# BW1098OBC_Power_Supply.net
KiCad netlist of a schematic drawn in Altium Designer
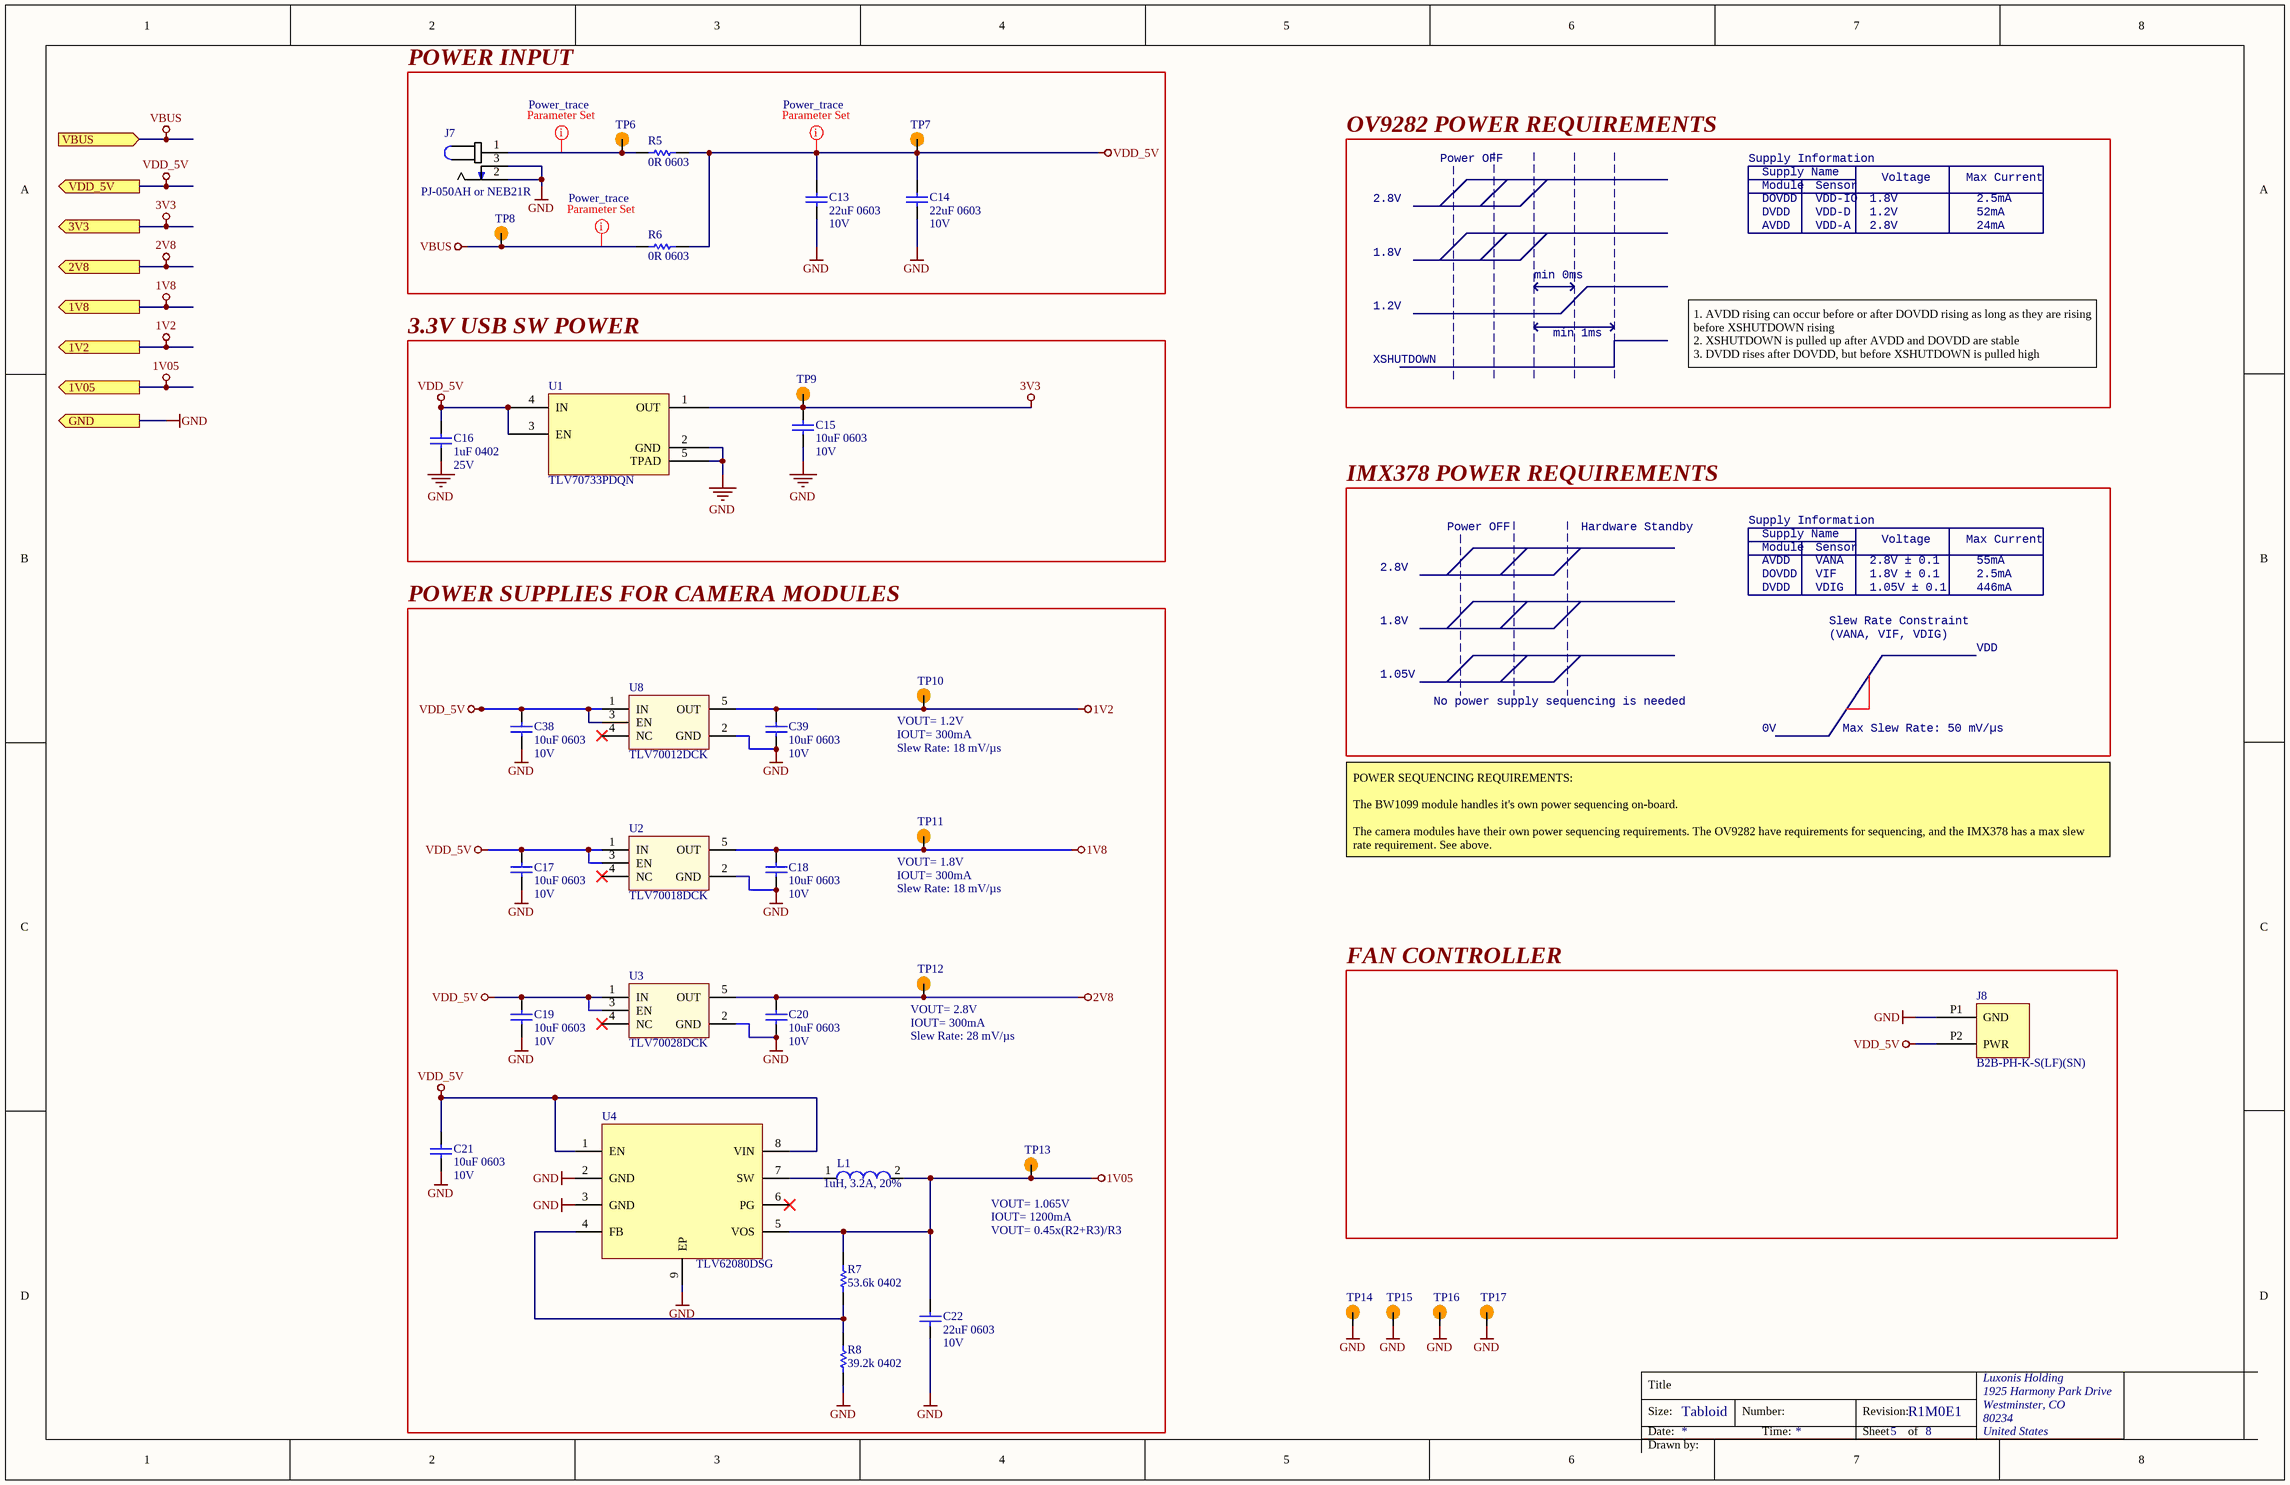
[diagram p0: BW1098OBC_Power_Supply.SchDoc]

(export (version "E")
  (design (tool "Eeschema 10.0.6"))
  (components
    (comp (ref "C13")
      (value "22uF 0603")
      (footprint "CAP_Altium_Vault_Generic:CAPC0603(1608)100_L")
      (description "CAP CER 22UF 10V X5R 0603 20%")
      (fields (field (name "TOLERANCE") "20%") (field (name "VOLTAGE RATING") "10V"))
      (libsource (lib "LuxonisMaster") (part "GRM188R61A226ME15D"))
    )
    (comp (ref "C14")
      (value "22uF 0603")
      (footprint "CAP_Altium_Vault_Generic:CAPC0603(1608)100_L")
      (description "CAP CER 22UF 10V X5R 0603 20%")
      (fields (field (name "TOLERANCE") "20%") (field (name "VOLTAGE RATING") "10V"))
      (libsource (lib "LuxonisMaster") (part "GRM188R61A226ME15D"))
    )
    (comp (ref "C15")
      (value "10uF 0603")
      (footprint "CAP_Altium_Vault_Generic:CAPC0603(1608)100_L")
      (description "CAP CER 10UF 10V X5R 0603 20%")
      (fields (field (name "TOLERANCE") "20%") (field (name "VOLTAGE RATING") "10V"))
      (libsource (lib "LuxonisMaster") (part "GRM188R61A106ME69D"))
    )
    (comp (ref "C16")
      (value "1uF 0402")
      (footprint "CAP_Altium_Vault_Generic:CAPC0402(1005)70_L")
      (description "CAP CER 1UF 25V X5R 0402 10%")
      (fields
        (field (name "TOLERANCE") "10%")
        (field (name "VOLTAGE") "25V")
        (field (name "VOLTAGE RATING") "25V")
      )
      (libsource (lib "LuxonisMaster") (part "GRM155R61E105KA12D"))
    )
    (comp (ref "C17")
      (value "10uF 0603")
      (footprint "CAP_Altium_Vault_Generic:CAPC0603(1608)100_L")
      (description "CAP CER 10UF 10V X5R 0603 20%")
      (fields (field (name "TOLERANCE") "20%") (field (name "VOLTAGE RATING") "10V"))
      (libsource (lib "LuxonisMaster") (part "GRM188R61A106ME69D"))
    )
    (comp (ref "C18")
      (value "10uF 0603")
      (footprint "CAP_Altium_Vault_Generic:CAPC0603(1608)100_L")
      (description "CAP CER 10UF 10V X5R 0603 20%")
      (fields (field (name "TOLERANCE") "20%") (field (name "VOLTAGE RATING") "10V"))
      (libsource (lib "LuxonisMaster") (part "GRM188R61A106ME69D"))
    )
    (comp (ref "C19")
      (value "10uF 0603")
      (footprint "CAP_Altium_Vault_Generic:CAPC0603(1608)100_L")
      (description "CAP CER 10UF 10V X5R 0603 20%")
      (fields (field (name "TOLERANCE") "20%") (field (name "VOLTAGE RATING") "10V"))
      (libsource (lib "LuxonisMaster") (part "GRM188R61A106ME69D"))
    )
    (comp (ref "C20")
      (value "10uF 0603")
      (footprint "CAP_Altium_Vault_Generic:CAPC0603(1608)100_L")
      (description "CAP CER 10UF 10V X5R 0603 20%")
      (fields (field (name "TOLERANCE") "20%") (field (name "VOLTAGE RATING") "10V"))
      (libsource (lib "LuxonisMaster") (part "GRM188R61A106ME69D"))
    )
    (comp (ref "C21")
      (value "10uF 0603")
      (footprint "CAP_Altium_Vault_Generic:CAPC0603(1608)100_L")
      (description "CAP CER 10UF 10V X5R 0603 20%")
      (fields (field (name "TOLERANCE") "20%") (field (name "VOLTAGE RATING") "10V"))
      (libsource (lib "LuxonisMaster") (part "GRM188R61A106ME69D"))
    )
    (comp (ref "C22")
      (value "22uF 0603")
      (footprint "CAP_Altium_Vault_Generic:CAPC0603(1608)100_L")
      (description "CAP CER 22UF 10V X5R 0603 20%")
      (fields (field (name "TOLERANCE") "20%") (field (name "VOLTAGE RATING") "10V"))
      (libsource (lib "LuxonisMaster") (part "GRM188R61A226ME15D"))
    )
    (comp (ref "C38")
      (value "10uF 0603")
      (footprint "CAP_Altium_Vault_Generic:CAPC0603(1608)100_L")
      (description "CAP CER 10UF 10V X5R 0603 20%")
      (fields (field (name "TOLERANCE") "20%") (field (name "VOLTAGE RATING") "10V"))
      (libsource (lib "LuxonisMaster") (part "GRM188R61A106ME69D"))
    )
    (comp (ref "C39")
      (value "10uF 0603")
      (footprint "CAP_Altium_Vault_Generic:CAPC0603(1608)100_L")
      (description "CAP CER 10UF 10V X5R 0603 20%")
      (fields (field (name "TOLERANCE") "20%") (field (name "VOLTAGE RATING") "10V"))
      (libsource (lib "LuxonisMaster") (part "GRM188R61A106ME69D"))
    )
    (comp (ref "J7")
      (value "PJ-050AH or NEB21R")
      (footprint "LuxonisMaster:PJ-050AH/NEB21R_COMBO")
      (description "CONN POWER PIN 2 POS RA PTH Barrel jack 2.1mm x 5.5mm combo footprint")
      (libsource (lib "LuxonisMaster") (part "PJ-050AH/NEB21R_COMBO"))
    )
    (comp (ref "J8")
      (value "B2B-PH-K-S(LF)(SN)")
      (footprint "LuxonisMaster:B2B-PH-K-S(LF)(SN)")
      (description "CONN HEADER VERT 2POS 2MM")
      (fields (field (name "MANUFACTURER") "JST"))
      (libsource (lib "LuxonisMaster") (part "B2B-PH-K-S(LF)(SN)"))
    )
    (comp (ref "L1")
      (value "1uH, 3.2A, 20%")
      (footprint "LuxonisMaster:DFE252012P-1R0M=P2")
      (description "FIXED IND 1UH 3.2A 42 MOHM SMD")
      (fields
        (field (name "MANUFACTURER") "Murata")
        (field (name "MANUFACTURER PART NUMBER") "DFE252012P-1R0M=P2")
      )
      (libsource (lib "LuxonisMaster") (part "DFE252012P-1R0M=P2"))
    )
    (comp (ref "R5")
      (value "0R 0603")
      (footprint "RES_Altium_Vault_Generic:RESC0603(1608)_N")
      (fields (field (name "TOLERANCE") "5%"))
      (libsource (lib "LuxonisMaster") (part "CRCW06030000Z0EA"))
    )
    (comp (ref "R6")
      (value "0R 0603")
      (footprint "RES_Altium_Vault_Generic:RESC0603(1608)_N")
      (fields (field (name "TOLERANCE") "5%"))
      (libsource (lib "LuxonisMaster") (part "CRCW06030000Z0EA"))
    )
    (comp (ref "R7")
      (value "53.6k 0402")
      (footprint "RES_Altium_Vault_Generic:RESC0402(1005)_L")
      (description "RES SMD 53.6K OHM 1% 1/16W 0402")
      (fields (field (name "TOLERANCE") "1%"))
      (libsource (lib "LuxonisMaster") (part "CRCW040253K6FKED"))
    )
    (comp (ref "R8")
      (value "39.2k 0402")
      (footprint "RES_Altium_Vault_Generic:RESC0402(1005)_L")
      (description "RES SMD 39.2K OHM 1% 1/16W 0402")
      (fields (field (name "TOLERANCE") "1%"))
      (libsource (lib "LuxonisMaster") (part "CRCW040239K2FKED"))
    )
    (comp (ref "TP6")
      (value "TP100_200_NS")
      (footprint "LuxonisMaster:TP100_200_NS")
      (libsource (lib "LuxonisMaster") (part "TEST_POINT"))
    )
    (comp (ref "TP7")
      (value "TP100_200_NS")
      (footprint "LuxonisMaster:TP100_200_NS")
      (libsource (lib "LuxonisMaster") (part "TEST_POINT"))
    )
    (comp (ref "TP8")
      (value "TP100_200_NS")
      (footprint "LuxonisMaster:TP100_200_NS")
      (libsource (lib "LuxonisMaster") (part "TEST_POINT"))
    )
    (comp (ref "TP9")
      (value "TP100_200_NS")
      (footprint "LuxonisMaster:TP100_200_NS")
      (libsource (lib "LuxonisMaster") (part "TEST_POINT"))
    )
    (comp (ref "TP10")
      (value "TP100_200_NS")
      (footprint "LuxonisMaster:TP100_200_NS")
      (libsource (lib "LuxonisMaster") (part "TEST_POINT"))
    )
    (comp (ref "TP11")
      (value "TP100_200_NS")
      (footprint "LuxonisMaster:TP100_200_NS")
      (libsource (lib "LuxonisMaster") (part "TEST_POINT"))
    )
    (comp (ref "TP12")
      (value "TP100_200_NS")
      (footprint "LuxonisMaster:TP100_200_NS")
      (libsource (lib "LuxonisMaster") (part "TEST_POINT"))
    )
    (comp (ref "TP13")
      (value "TP100_200_NS")
      (footprint "LuxonisMaster:TP100_200_NS")
      (libsource (lib "LuxonisMaster") (part "TEST_POINT"))
    )
    (comp (ref "TP14")
      (value "TP100_200_NS")
      (footprint "LuxonisMaster:TP100_200_NS")
      (libsource (lib "LuxonisMaster") (part "TEST_POINT"))
    )
    (comp (ref "TP15")
      (value "TP100_200_NS")
      (footprint "LuxonisMaster:TP100_200_NS")
      (libsource (lib "LuxonisMaster") (part "TEST_POINT"))
    )
    (comp (ref "TP16")
      (value "TP100_200_NS")
      (footprint "LuxonisMaster:TP100_200_NS")
      (libsource (lib "LuxonisMaster") (part "TEST_POINT"))
    )
    (comp (ref "TP17")
      (value "TP100_200_NS")
      (footprint "LuxonisMaster:TP100_200_NS")
      (libsource (lib "LuxonisMaster") (part "TEST_POINT"))
    )
    (comp (ref "U1")
      (value "TLV70733PDQN")
      (footprint "LuxonisMaster:TLV70733PDQN")
      (description "IC REG LINEAR 3.3V 200MA 4X2SON Linear Voltage Regulator IC  1 Output  200mA 4-X2SON (1x1)")
      (fields
        (field (name "MANUFACTURER") "Texas Instruments")
        (field (name "MANUFACTURER PART NUMBER") "TLV70710DQN")
      )
      (libsource (lib "LuxonisMaster") (part "TLV70733PDQN"))
    )
    (comp (ref "U2")
      (value "TLV70018DCK")
      (footprint "LuxonisMaster:TLV70018DCK")
      (description "IC REG LINEAR 1.8V 200MA SC70-5 Linear Voltage Regulator IC  1 Output  200mA SC-70-5")
      (libsource (lib "LuxonisMaster") (part "TLV70018DCK"))
    )
    (comp (ref "U3")
      (value "TLV70028DCK")
      (footprint "LuxonisMaster:TLV70028DCK")
      (description "IC REG LINEAR 2.8V 200MA SC70-5 Linear Voltage Regulator IC  1 Output  200mA SC-70-5")
      (libsource (lib "LuxonisMaster") (part "TLV70028DCK"))
    )
    (comp (ref "U4")
      (value "TLV62080DSG")
      (footprint "LuxonisMaster:TLV62080DSG")
      (description "IC REG BUCK ADJ 1.2A SYNC 8WSON")
      (libsource (lib "LuxonisMaster") (part "TLV62080DSG"))
    )
    (comp (ref "U8")
      (value "TLV70012DCK")
      (footprint "LuxonisMaster:TLV70012DCK")
      (description "IC REG LINEAR 1.2V 200MA SC70-5")
      (libsource (lib "LuxonisMaster") (part "TLV70012DCK"))
    )
  )
  (nets
    (net (code "1") (name "1V2") (class "Default")
      (node (ref "C39") (pin "2") (pinfunction "2_2") (pintype "passive"))
      (node (ref "TP10") (pin "1") (pintype "passive"))
      (node (ref "U8") (pin "5") (pinfunction "OUT_5") (pintype "passive"))
    )
    (net (code "2") (name "1V05") (class "Default")
      (node (ref "C22") (pin "2") (pinfunction "2_2") (pintype "passive"))
      (node (ref "L1") (pin "2") (pinfunction "2_2") (pintype "passive"))
      (node (ref "R7") (pin "2") (pinfunction "2_2") (pintype "passive"))
      (node (ref "TP13") (pin "1") (pintype "passive"))
      (node (ref "U4") (pin "5") (pinfunction "VOS_5") (pintype "passive"))
    )
    (net (code "3") (name "1V8") (class "Default")
      (node (ref "C18") (pin "2") (pinfunction "2_2") (pintype "passive"))
      (node (ref "TP11") (pin "1") (pintype "passive"))
      (node (ref "U2") (pin "5") (pinfunction "OUT_5") (pintype "passive"))
    )
    (net (code "4") (name "2V8") (class "Default")
      (node (ref "C20") (pin "2") (pinfunction "2_2") (pintype "passive"))
      (node (ref "TP12") (pin "1") (pintype "passive"))
      (node (ref "U3") (pin "5") (pinfunction "OUT_5") (pintype "passive"))
    )
    (net (code "5") (name "3V3") (class "Default")
      (node (ref "C15") (pin "2") (pinfunction "2_2") (pintype "passive"))
      (node (ref "TP9") (pin "1") (pintype "passive"))
      (node (ref "U1") (pin "1") (pinfunction "OUT_1") (pintype "power_in"))
    )
    (net (code "6") (name "GND") (class "Default")
      (node (ref "C13") (pin "1") (pinfunction "1_1") (pintype "passive"))
      (node (ref "C14") (pin "1") (pinfunction "1_1") (pintype "passive"))
      (node (ref "C15") (pin "1") (pinfunction "1_1") (pintype "passive"))
      (node (ref "C16") (pin "1") (pinfunction "1_1") (pintype "passive"))
      (node (ref "C17") (pin "1") (pinfunction "1_1") (pintype "passive"))
      (node (ref "C18") (pin "1") (pinfunction "1_1") (pintype "passive"))
      (node (ref "C19") (pin "1") (pinfunction "1_1") (pintype "passive"))
      (node (ref "C20") (pin "1") (pinfunction "1_1") (pintype "passive"))
      (node (ref "C21") (pin "1") (pinfunction "1_1") (pintype "passive"))
      (node (ref "C22") (pin "1") (pinfunction "1_1") (pintype "passive"))
      (node (ref "C38") (pin "1") (pinfunction "1_1") (pintype "passive"))
      (node (ref "C39") (pin "1") (pinfunction "1_1") (pintype "passive"))
      (node (ref "J7") (pin "2") (pinfunction "2_2") (pintype "passive"))
      (node (ref "J7") (pin "3") (pinfunction "3_3") (pintype "passive"))
      (node (ref "J8") (pin "P1") (pinfunction "GND_P1") (pintype "passive"))
      (node (ref "R8") (pin "1") (pinfunction "1_1") (pintype "passive"))
      (node (ref "TP14") (pin "1") (pintype "passive"))
      (node (ref "TP15") (pin "1") (pintype "passive"))
      (node (ref "TP16") (pin "1") (pintype "passive"))
      (node (ref "TP17") (pin "1") (pintype "passive"))
      (node (ref "U1") (pin "2") (pinfunction "GND_2") (pintype "power_in"))
      (node (ref "U1") (pin "5") (pinfunction "TPAD_5") (pintype "passive"))
      (node (ref "U2") (pin "2") (pinfunction "GND_2") (pintype "passive"))
      (node (ref "U3") (pin "2") (pinfunction "GND_2") (pintype "passive"))
      (node (ref "U4") (pin "2") (pinfunction "GND_2") (pintype "passive"))
      (node (ref "U4") (pin "3") (pinfunction "GND_3") (pintype "passive"))
      (node (ref "U4") (pin "9") (pinfunction "EP_9") (pintype "passive"))
      (node (ref "U8") (pin "2") (pinfunction "GND_2") (pintype "passive"))
    )
    (net (code "7") (name "Net-(J7-Pad1)") (class "Default")
      (node (ref "J7") (pin "1") (pinfunction "1_1") (pintype "passive"))
      (node (ref "R5") (pin "1") (pinfunction "1_1") (pintype "passive"))
      (node (ref "TP6") (pin "1") (pintype "passive"))
    )
    (net (code "8") (name "Net-(U4-FB)") (class "Default")
      (node (ref "R7") (pin "1") (pinfunction "1_1") (pintype "passive"))
      (node (ref "R8") (pin "2") (pinfunction "2_2") (pintype "passive"))
      (node (ref "U4") (pin "4") (pinfunction "FB_4") (pintype "passive"))
    )
    (net (code "9") (name "Net-(U4-SW)") (class "Default")
      (node (ref "L1") (pin "1") (pinfunction "1_1") (pintype "passive"))
      (node (ref "U4") (pin "7") (pinfunction "SW_7") (pintype "passive"))
    )
    (net (code "10") (name "VBUS") (class "Default")
      (node (ref "R6") (pin "1") (pinfunction "1_1") (pintype "passive"))
      (node (ref "TP8") (pin "1") (pintype "passive"))
    )
    (net (code "11") (name "VDD_5V") (class "Default")
      (node (ref "C13") (pin "2") (pinfunction "2_2") (pintype "passive"))
      (node (ref "C14") (pin "2") (pinfunction "2_2") (pintype "passive"))
      (node (ref "C16") (pin "2") (pinfunction "2_2") (pintype "passive"))
      (node (ref "C17") (pin "2") (pinfunction "2_2") (pintype "passive"))
      (node (ref "C19") (pin "2") (pinfunction "2_2") (pintype "passive"))
      (node (ref "C21") (pin "2") (pinfunction "2_2") (pintype "passive"))
      (node (ref "C38") (pin "2") (pinfunction "2_2") (pintype "passive"))
      (node (ref "J8") (pin "P2") (pinfunction "PWR_P2") (pintype "passive"))
      (node (ref "R5") (pin "2") (pinfunction "2_2") (pintype "passive"))
      (node (ref "R6") (pin "2") (pinfunction "2_2") (pintype "passive"))
      (node (ref "TP7") (pin "1") (pintype "passive"))
      (node (ref "U1") (pin "3") (pinfunction "EN_3") (pintype "power_in"))
      (node (ref "U1") (pin "4") (pinfunction "IN_4") (pintype "power_in"))
      (node (ref "U2") (pin "1") (pinfunction "IN_1") (pintype "passive"))
      (node (ref "U2") (pin "3") (pinfunction "EN_3") (pintype "passive"))
      (node (ref "U3") (pin "1") (pinfunction "IN_1") (pintype "passive"))
      (node (ref "U3") (pin "3") (pinfunction "EN_3") (pintype "passive"))
      (node (ref "U4") (pin "1") (pinfunction "EN_1") (pintype "passive"))
      (node (ref "U4") (pin "8") (pinfunction "VIN_8") (pintype "passive"))
      (node (ref "U8") (pin "1") (pinfunction "IN_1") (pintype "passive"))
      (node (ref "U8") (pin "3") (pinfunction "EN_3") (pintype "passive"))
    )
    (net (code "12") (name "unconnected-(U2-NC-Pad4)") (class "Default")
      (node (ref "U2") (pin "4") (pinfunction "NC_4") (pintype "passive+no_connect"))
    )
    (net (code "13") (name "unconnected-(U3-NC-Pad4)") (class "Default")
      (node (ref "U3") (pin "4") (pinfunction "NC_4") (pintype "passive+no_connect"))
    )
    (net (code "14") (name "unconnected-(U4-PG-Pad6)") (class "Default")
      (node (ref "U4") (pin "6") (pinfunction "PG_6") (pintype "passive+no_connect"))
    )
    (net (code "15") (name "unconnected-(U8-NC-Pad4)") (class "Default")
      (node (ref "U8") (pin "4") (pinfunction "NC_4") (pintype "passive+no_connect"))
    )
  )
)
